# ADC_UART_RX_V1.net
KiCad netlist of a schematic drawn in Altium Designer
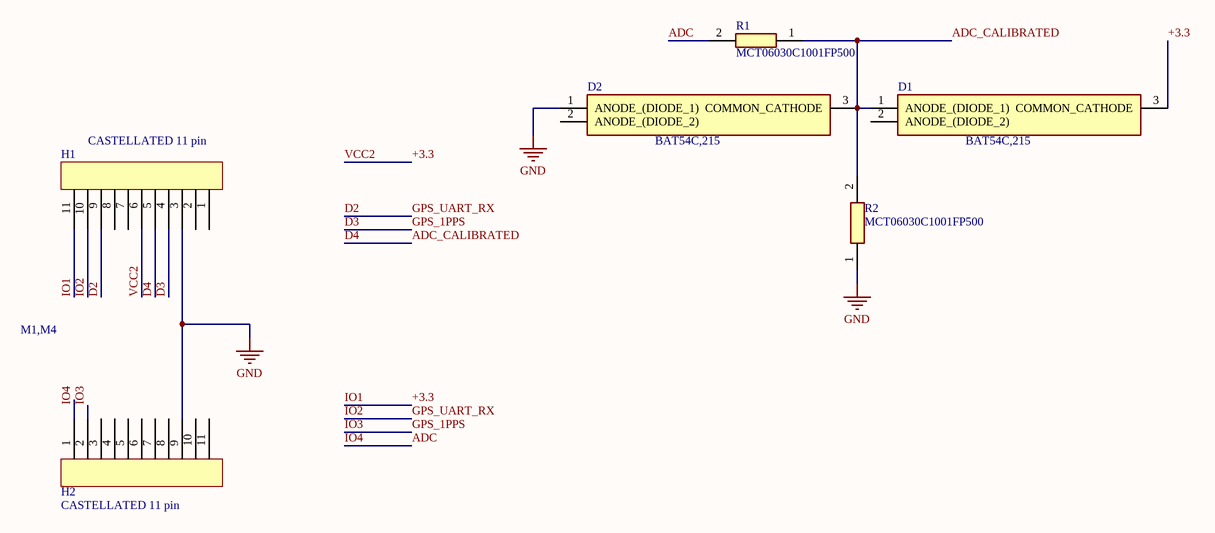
[diagram p0: ADC_UART_RX_V1.SchDoc]

(export (version "E")
  (design (tool "Eeschema 10.0.6"))
  (components
    (comp (ref "D1")
      (value "BAT54C,215")
      (footprint "SamacSys:SOT95P230X110-3N")
      (description "Diode")
      (fields (field (name "MOUSER2 PART NUMBER") "771-BAT54C-T/R"))
      (libsource (lib "*") (part "BAT54C,215"))
    )
    (comp (ref "D2")
      (value "BAT54C,215")
      (footprint "SamacSys:SOT95P230X110-3N")
      (description "Diode")
      (fields (field (name "MOUSER2 PART NUMBER") "771-BAT54C-T/R"))
      (libsource (lib "*") (part "BAT54C,215"))
    )
    (comp (ref "H1")
      (value "CASTELLATED 11 pin")
      (footprint "CASTELLATED 11 pin")
      (libsource (lib "") (part "CASTELLATED 11 pin_1"))
    )
    (comp (ref "H2")
      (value "CASTELLATED 11 pin")
      (footprint "CASTELLATED 11 pin")
      (libsource (lib "USIB") (part "CASTELLATED 11 pin"))
    )
    (comp (ref "R1")
      (value "MCT06030C1001FP500")
      (footprint "SamacSys:RESC1608X55N")
      (description "Resistor")
      (libsource (lib "") (part "MCT06030C1001FP500_1"))
    )
    (comp (ref "R2")
      (value "MCT06030C1001FP500")
      (footprint "SamacSys:RESC1608X55N")
      (description "Resistor")
      (libsource (lib "*") (part "MCT06030C1001FP500"))
    )
  )
  (nets
    (net (code "1") (name "/+3.3") (class "Default")
      (node (ref "D1") (pin "3") (pinfunction "COMMON_CATHODE_3") (pintype "passive"))
      (node (ref "H1") (pin "11") (pintype "passive"))
      (node (ref "H1") (pin "6") (pintype "passive"))
    )
    (net (code "2") (name "/ADC") (class "Default")
      (node (ref "H2") (pin "1") (pintype "passive"))
      (node (ref "R1") (pin "2") (pinfunction "2_2") (pintype "passive"))
    )
    (net (code "3") (name "/ADC_CALIBRATED") (class "Default")
      (node (ref "D1") (pin "1") (pinfunction "ANODE_(DIODE_1)_1") (pintype "passive"))
      (node (ref "D2") (pin "3") (pinfunction "COMMON_CATHODE_3") (pintype "passive"))
      (node (ref "H1") (pin "5") (pintype "passive"))
      (node (ref "R1") (pin "1") (pinfunction "1_1") (pintype "passive"))
      (node (ref "R2") (pin "2") (pinfunction "2_2") (pintype "passive"))
    )
    (net (code "4") (name "/D2") (class "Default")
      (node (ref "H1") (pin "10") (pintype "passive"))
      (node (ref "H1") (pin "9") (pintype "passive"))
    )
    (net (code "5") (name "/D3") (class "Default")
      (node (ref "H1") (pin "4") (pintype "passive"))
      (node (ref "H2") (pin "2") (pintype "passive"))
    )
    (net (code "6") (name "GND") (class "Default")
      (node (ref "D2") (pin "1") (pinfunction "ANODE_(DIODE_1)_1") (pintype "passive"))
      (node (ref "H1") (pin "3") (pintype "passive"))
      (node (ref "H2") (pin "9") (pintype "passive"))
      (node (ref "R2") (pin "1") (pinfunction "1_1") (pintype "passive"))
    )
    (net (code "7") (name "unconnected-(D1-ANODE_(DIODE_2)-Pad2)") (class "Default")
      (node (ref "D1") (pin "2") (pinfunction "ANODE_(DIODE_2)_2") (pintype "passive"))
    )
    (net (code "8") (name "unconnected-(D2-ANODE_(DIODE_2)-Pad2)") (class "Default")
      (node (ref "D2") (pin "2") (pinfunction "ANODE_(DIODE_2)_2") (pintype "passive"))
    )
    (net (code "9") (name "unconnected-(H1-Pad1)") (class "Default")
      (node (ref "H1") (pin "1") (pintype "passive"))
    )
    (net (code "10") (name "unconnected-(H1-Pad2)") (class "Default")
      (node (ref "H1") (pin "2") (pintype "passive"))
    )
    (net (code "11") (name "unconnected-(H1-Pad7)") (class "Default")
      (node (ref "H1") (pin "7") (pintype "passive"))
    )
    (net (code "12") (name "unconnected-(H1-Pad8)") (class "Default")
      (node (ref "H1") (pin "8") (pintype "passive"))
    )
    (net (code "13") (name "unconnected-(H2-Pad3)") (class "Default")
      (node (ref "H2") (pin "3") (pintype "passive"))
    )
    (net (code "14") (name "unconnected-(H2-Pad4)") (class "Default")
      (node (ref "H2") (pin "4") (pintype "passive"))
    )
    (net (code "15") (name "unconnected-(H2-Pad5)") (class "Default")
      (node (ref "H2") (pin "5") (pintype "passive"))
    )
    (net (code "16") (name "unconnected-(H2-Pad6)") (class "Default")
      (node (ref "H2") (pin "6") (pintype "passive"))
    )
    (net (code "17") (name "unconnected-(H2-Pad7)") (class "Default")
      (node (ref "H2") (pin "7") (pintype "passive"))
    )
    (net (code "18") (name "unconnected-(H2-Pad8)") (class "Default")
      (node (ref "H2") (pin "8") (pintype "passive"))
    )
    (net (code "19") (name "unconnected-(H2-Pad10)") (class "Default")
      (node (ref "H2") (pin "10") (pintype "passive"))
    )
    (net (code "20") (name "unconnected-(H2-Pad11)") (class "Default")
      (node (ref "H2") (pin "11") (pintype "passive"))
    )
  )
)
